# ecg_final.net
KiCad netlist of a schematic drawn in EAGLE
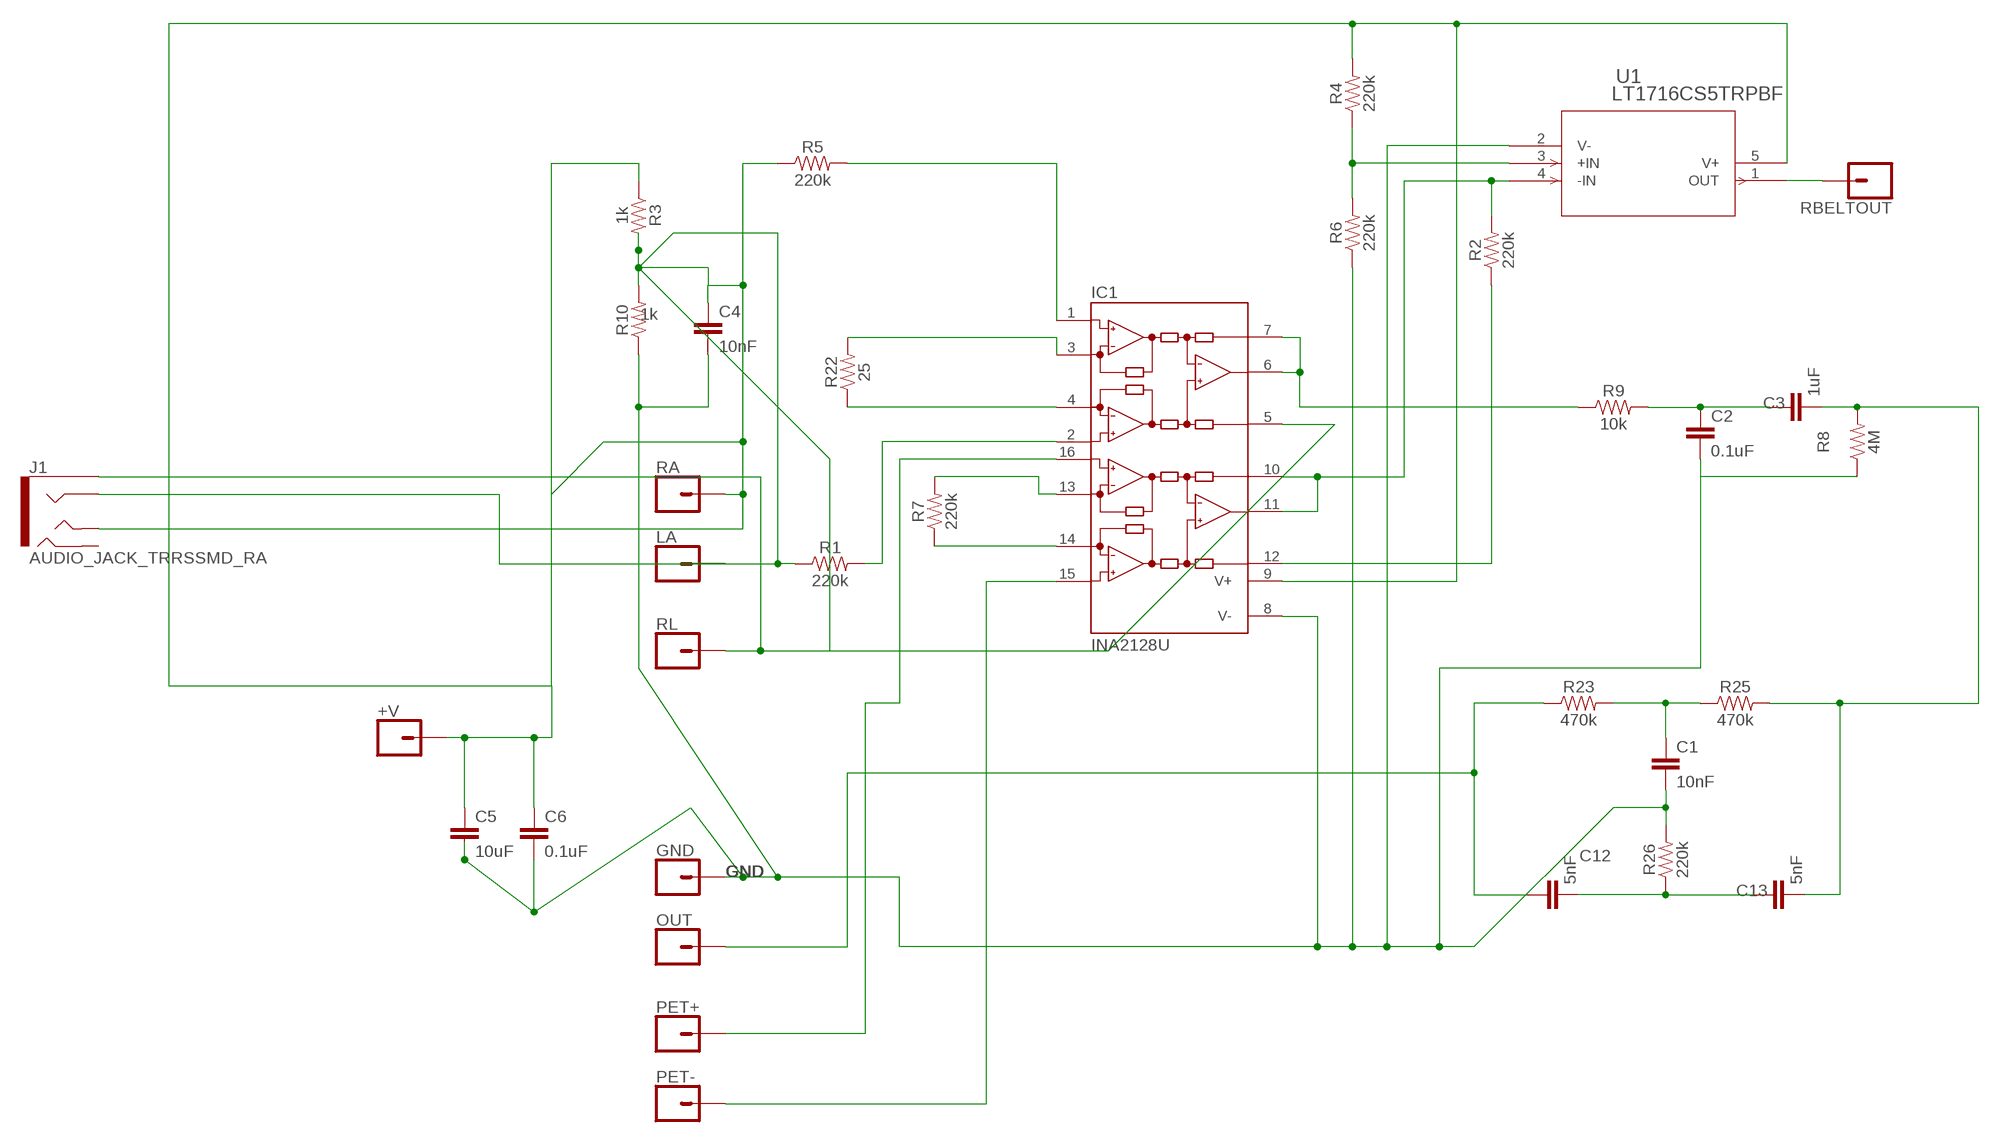
[diagram p0: schematic, sheet 1]

(export (version "E")
  (design (tool "Eeschema 10.0.6"))
  (components
    (comp (ref "+V")
      (value "CONN_01")
      (footprint "eagle-import:1X01")
      (libsource (lib "eagle-import") (part "CONN_01"))
    )
    (comp (ref "C1")
      (value "10nF")
      (footprint "eagle-import:CAP-PTH-10MM")
      (libsource (lib "eagle-import") (part "10NF-PTH-10MM-10000V-1-%"))
    )
    (comp (ref "C2")
      (value "0.1uF")
      (footprint "eagle-import:CAP-PTH-10MM")
      (libsource (lib "eagle-import") (part "10NF-PTH-10MM-10000V-1-%"))
    )
    (comp (ref "C3")
      (value "1uF")
      (footprint "eagle-import:CAP-PTH-10MM")
      (libsource (lib "eagle-import") (part "10NF-PTH-10MM-10000V-1-%"))
    )
    (comp (ref "C4")
      (value "10nF")
      (footprint "eagle-import:CAP-PTH-10MM")
      (libsource (lib "eagle-import") (part "10NF-PTH-10MM-10000V-1-%"))
    )
    (comp (ref "C5")
      (value "10uF")
      (footprint "eagle-import:CAP-PTH-10MM")
      (libsource (lib "eagle-import") (part "10NF-PTH-10MM-10000V-1-%"))
    )
    (comp (ref "C6")
      (value "0.1uF")
      (footprint "eagle-import:CAP-PTH-10MM")
      (libsource (lib "eagle-import") (part "10NF-PTH-10MM-10000V-1-%"))
    )
    (comp (ref "C12")
      (value "5nF")
      (footprint "eagle-import:CAP-PTH-10MM")
      (libsource (lib "eagle-import") (part "10NF-PTH-10MM-10000V-1-%"))
    )
    (comp (ref "C13")
      (value "5nF")
      (footprint "eagle-import:CAP-PTH-10MM")
      (libsource (lib "eagle-import") (part "10NF-PTH-10MM-10000V-1-%"))
    )
    (comp (ref "GND")
      (value "CONN_01")
      (footprint "eagle-import:1X01")
      (libsource (lib "eagle-import") (part "CONN_01"))
    )
    (comp (ref "IC1")
      (value "INA2128U")
      (footprint "eagle-import:SO16-1")
      (fields (field (name "MF") "TEXAS INSTRUMENTS"))
      (libsource (lib "eagle-import") (part "INA2128U"))
    )
    (comp (ref "J1")
      (value "AUDIO_JACK_TRRSSMD_RA")
      (footprint "eagle-import:AUDIO_JACK_3.5MM_TRRS_SMD_RA")
      (libsource (lib "eagle-import") (part "AUDIO_JACK_TRRSSMD_RA"))
    )
    (comp (ref "LA")
      (value "CONN_01")
      (footprint "eagle-import:1X01")
      (libsource (lib "eagle-import") (part "CONN_01"))
    )
    (comp (ref "OUT")
      (value "CONN_01")
      (footprint "eagle-import:1X01")
      (libsource (lib "eagle-import") (part "CONN_01"))
    )
    (comp (ref "PET+")
      (value "CONN_01")
      (footprint "eagle-import:1X01")
      (libsource (lib "eagle-import") (part "CONN_01"))
    )
    (comp (ref "PET-")
      (value "CONN_01")
      (footprint "eagle-import:1X01")
      (libsource (lib "eagle-import") (part "CONN_01"))
    )
    (comp (ref "R1")
      (value "220k")
      (footprint "eagle-import:AXIAL-0.3")
      (libsource (lib "eagle-import") (part "10KOHM-HORIZ-1/4W-1%"))
    )
    (comp (ref "R2")
      (value "220k")
      (footprint "eagle-import:AXIAL-0.3")
      (libsource (lib "eagle-import") (part "10KOHM-HORIZ-1/4W-1%"))
    )
    (comp (ref "R3")
      (value "1k")
      (footprint "eagle-import:AXIAL-0.3")
      (libsource (lib "eagle-import") (part "1KOHM-HORIZ-1/4W-1%"))
    )
    (comp (ref "R4")
      (value "220k")
      (footprint "eagle-import:AXIAL-0.3")
      (libsource (lib "eagle-import") (part "10KOHM-HORIZ-1/4W-1%"))
    )
    (comp (ref "R5")
      (value "220k")
      (footprint "eagle-import:AXIAL-0.3")
      (libsource (lib "eagle-import") (part "10KOHM-HORIZ-1/4W-1%"))
    )
    (comp (ref "R6")
      (value "220k")
      (footprint "eagle-import:AXIAL-0.3")
      (libsource (lib "eagle-import") (part "10KOHM-HORIZ-1/4W-1%"))
    )
    (comp (ref "R7")
      (value "220k")
      (footprint "eagle-import:AXIAL-0.3")
      (libsource (lib "eagle-import") (part "10KOHM-HORIZ-1/4W-1%"))
    )
    (comp (ref "R8")
      (value "4M")
      (footprint "eagle-import:AXIAL-0.3")
      (libsource (lib "eagle-import") (part "1KOHM-HORIZ-1/4W-1%"))
    )
    (comp (ref "R9")
      (value "10k")
      (footprint "eagle-import:AXIAL-0.3")
      (libsource (lib "eagle-import") (part "1KOHM-HORIZ-1/4W-1%"))
    )
    (comp (ref "R10")
      (value "1k")
      (footprint "eagle-import:AXIAL-0.3")
      (libsource (lib "eagle-import") (part "1KOHM-HORIZ-1/4W-1%"))
    )
    (comp (ref "R22")
      (value "25")
      (footprint "eagle-import:AXIAL-0.3")
      (libsource (lib "eagle-import") (part "1KOHM-HORIZ-1/4W-5%"))
    )
    (comp (ref "R23")
      (value "470k")
      (footprint "eagle-import:AXIAL-0.3")
      (libsource (lib "eagle-import") (part "1KOHM-HORIZ-1/4W-5%"))
    )
    (comp (ref "R25")
      (value "470k")
      (footprint "eagle-import:AXIAL-0.3")
      (libsource (lib "eagle-import") (part "1KOHM-HORIZ-1/4W-5%"))
    )
    (comp (ref "R26")
      (value "220k")
      (footprint "eagle-import:AXIAL-0.3")
      (libsource (lib "eagle-import") (part "1KOHM-HORIZ-1/4W-5%"))
    )
    (comp (ref "RA")
      (value "CONN_01")
      (footprint "eagle-import:1X01")
      (libsource (lib "eagle-import") (part "CONN_01"))
    )
    (comp (ref "RBELTOUT")
      (value "CONN_01")
      (footprint "eagle-import:1X01")
      (libsource (lib "eagle-import") (part "CONN_01"))
    )
    (comp (ref "RL")
      (value "CONN_01")
      (footprint "eagle-import:1X01")
      (libsource (lib "eagle-import") (part "CONN_01"))
    )
    (comp (ref "U1")
      (value "LT1716CS5TRPBF")
      (footprint "eagle-import:SOT-5_S")
      (fields
        (field (name "DIGI-KEY_PART_NUMBER") "LT1716CS5#TRPBFCT-ND")
        (field (name "MF") "Linear Technology")
        (field (name "MP") "LT1716CS5#TRPBF")
      )
      (libsource (lib "eagle-import") (part "LT1716CS5TRPBF"))
    )
  )
  (nets
    (net (code "1") (name "/GND") (class "Default")
      (node (ref "C1") (pin "2") (pinfunction "2_2") (pintype "passive"))
      (node (ref "C2") (pin "2") (pinfunction "2_2") (pintype "passive"))
      (node (ref "C4") (pin "2") (pinfunction "2_2") (pintype "passive"))
      (node (ref "C5") (pin "2") (pinfunction "2_2") (pintype "passive"))
      (node (ref "C6") (pin "2") (pinfunction "2_2") (pintype "passive"))
      (node (ref "GND") (pin "1") (pinfunction "1_1") (pintype "passive"))
      (node (ref "IC1") (pin "8") (pinfunction "V-_8") (pintype "power_in"))
      (node (ref "R10") (pin "P$1") (pinfunction "1_P$1") (pintype "passive"))
      (node (ref "R26") (pin "P$2") (pinfunction "2_P$2") (pintype "passive"))
      (node (ref "R6") (pin "P$1") (pinfunction "1_P$1") (pintype "passive"))
      (node (ref "R8") (pin "P$1") (pinfunction "1_P$1") (pintype "passive"))
      (node (ref "U1") (pin "2") (pinfunction "V-_2") (pintype "power_in"))
    )
    (net (code "2") (name "Net-(IC1-INA+)") (class "Default")
      (node (ref "IC1") (pin "2") (pinfunction "INA+_2") (pintype "input"))
      (node (ref "R1") (pin "P$2") (pinfunction "2_P$2") (pintype "passive"))
    )
    (net (code "3") (name "Net-(IC1-INA-)") (class "Default")
      (node (ref "IC1") (pin "1") (pinfunction "INA-_1") (pintype "input"))
      (node (ref "R5") (pin "P$2") (pinfunction "2_P$2") (pintype "passive"))
    )
    (net (code "4") (name "Net-(IC1-INB+)") (class "Default")
      (node (ref "IC1") (pin "15") (pinfunction "INB+_15") (pintype "input"))
      (node (ref "PET-") (pin "1") (pinfunction "1_1") (pintype "passive"))
    )
    (net (code "5") (name "Net-(IC1-INB-)") (class "Default")
      (node (ref "IC1") (pin "16") (pinfunction "INB-_16") (pintype "input"))
      (node (ref "PET+") (pin "1") (pinfunction "1_1") (pintype "passive"))
    )
    (net (code "6") (name "Net-(IC1-REFA)") (class "Default")
      (node (ref "C4") (pin "1") (pinfunction "1_1") (pintype "passive"))
      (node (ref "IC1") (pin "5") (pinfunction "REFA_5") (pintype "input"))
      (node (ref "J1") (pin "EARTH") (pinfunction "EARTH_EARTH") (pintype "bidirectional"))
      (node (ref "J1") (pin "RING1") (pinfunction "RING1_RING1") (pintype "bidirectional"))
      (node (ref "J1") (pin "TIP") (pinfunction "TIP_TIP") (pintype "bidirectional"))
      (node (ref "LA") (pin "1") (pinfunction "1_1") (pintype "passive"))
      (node (ref "R1") (pin "P$1") (pinfunction "1_P$1") (pintype "passive"))
      (node (ref "R10") (pin "P$2") (pinfunction "2_P$2") (pintype "passive"))
      (node (ref "R3") (pin "P$2") (pinfunction "2_P$2") (pintype "passive"))
      (node (ref "R5") (pin "P$1") (pinfunction "1_P$1") (pintype "passive"))
      (node (ref "RA") (pin "1") (pinfunction "1_1") (pintype "passive"))
      (node (ref "RL") (pin "1") (pinfunction "1_1") (pintype "passive"))
    )
    (net (code "7") (name "Net-(IC1-REFB)") (class "Default")
      (node (ref "IC1") (pin "12") (pinfunction "REFB_12") (pintype "input"))
      (node (ref "R2") (pin "P$1") (pinfunction "1_P$1") (pintype "passive"))
    )
    (net (code "8") (name "Net-(IC1-SENSEA)") (class "Default")
      (node (ref "IC1") (pin "6") (pinfunction "VOA_6") (pintype "output"))
      (node (ref "IC1") (pin "7") (pinfunction "SENSEA_7") (pintype "input"))
      (node (ref "R9") (pin "P$1") (pinfunction "1_P$1") (pintype "passive"))
    )
    (net (code "9") (name "Net-(IC1-SENSEB)") (class "Default")
      (node (ref "IC1") (pin "10") (pinfunction "SENSEB_10") (pintype "input"))
      (node (ref "IC1") (pin "11") (pinfunction "VOB_11") (pintype "output"))
      (node (ref "R2") (pin "P$2") (pinfunction "2_P$2") (pintype "passive"))
      (node (ref "U1") (pin "4") (pinfunction "-IN_4") (pintype "input"))
    )
    (net (code "10") (name "Net-(IC1-V+)") (class "Default")
      (node (ref "+V") (pin "1") (pinfunction "1_1") (pintype "passive"))
      (node (ref "C5") (pin "1") (pinfunction "1_1") (pintype "passive"))
      (node (ref "C6") (pin "1") (pinfunction "1_1") (pintype "passive"))
      (node (ref "IC1") (pin "9") (pinfunction "V+_9") (pintype "power_in"))
      (node (ref "R3") (pin "P$1") (pinfunction "1_P$1") (pintype "passive"))
      (node (ref "R4") (pin "P$2") (pinfunction "2_P$2") (pintype "passive"))
      (node (ref "U1") (pin "5") (pinfunction "V+_5") (pintype "power_in"))
    )
    (net (code "11") (name "Net-(R4-1)") (class "Default")
      (node (ref "R4") (pin "P$1") (pinfunction "1_P$1") (pintype "passive"))
      (node (ref "R6") (pin "P$2") (pinfunction "2_P$2") (pintype "passive"))
      (node (ref "U1") (pin "3") (pinfunction "+IN_3") (pintype "input"))
    )
    (net (code "12") (name "Net-(R7-1)") (class "Default")
      (node (ref "IC1") (pin "14") (pinfunction "RGB_14") (pintype "passive"))
      (node (ref "R7") (pin "P$1") (pinfunction "1_P$1") (pintype "passive"))
    )
    (net (code "13") (name "Net-(R7-2)") (class "Default")
      (node (ref "IC1") (pin "13") (pinfunction "RGB_13") (pintype "passive"))
      (node (ref "R7") (pin "P$2") (pinfunction "2_P$2") (pintype "passive"))
    )
    (net (code "14") (name "Net-(R9-2)") (class "Default")
      (node (ref "C2") (pin "1") (pinfunction "1_1") (pintype "passive"))
      (node (ref "C3") (pin "1") (pinfunction "1_1") (pintype "passive"))
      (node (ref "R9") (pin "P$2") (pinfunction "2_P$2") (pintype "passive"))
    )
    (net (code "15") (name "Net-(R22-1)") (class "Default")
      (node (ref "IC1") (pin "4") (pinfunction "RGA_4") (pintype "passive"))
      (node (ref "R22") (pin "P$1") (pinfunction "1_P$1") (pintype "passive"))
    )
    (net (code "16") (name "Net-(R22-2)") (class "Default")
      (node (ref "IC1") (pin "3") (pinfunction "RGA_3") (pintype "passive"))
      (node (ref "R22") (pin "P$2") (pinfunction "2_P$2") (pintype "passive"))
    )
    (net (code "17") (name "Net-(R23-1)") (class "Default")
      (node (ref "C12") (pin "1") (pinfunction "1_1") (pintype "passive"))
      (node (ref "OUT") (pin "1") (pinfunction "1_1") (pintype "passive"))
      (node (ref "R23") (pin "P$1") (pinfunction "1_P$1") (pintype "passive"))
    )
    (net (code "18") (name "Net-(R23-2)") (class "Default")
      (node (ref "C1") (pin "1") (pinfunction "1_1") (pintype "passive"))
      (node (ref "R23") (pin "P$2") (pinfunction "2_P$2") (pintype "passive"))
      (node (ref "R25") (pin "P$1") (pinfunction "1_P$1") (pintype "passive"))
    )
    (net (code "19") (name "Net-(R25-2)") (class "Default")
      (node (ref "C13") (pin "2") (pinfunction "2_2") (pintype "passive"))
      (node (ref "C3") (pin "2") (pinfunction "2_2") (pintype "passive"))
      (node (ref "R25") (pin "P$2") (pinfunction "2_P$2") (pintype "passive"))
      (node (ref "R8") (pin "P$2") (pinfunction "2_P$2") (pintype "passive"))
    )
    (net (code "20") (name "Net-(R26-1)") (class "Default")
      (node (ref "C12") (pin "2") (pinfunction "2_2") (pintype "passive"))
      (node (ref "C13") (pin "1") (pinfunction "1_1") (pintype "passive"))
      (node (ref "R26") (pin "P$1") (pinfunction "1_P$1") (pintype "passive"))
    )
    (net (code "21") (name "Net-(U1-OUT)") (class "Default")
      (node (ref "RBELTOUT") (pin "1") (pinfunction "1_1") (pintype "passive"))
      (node (ref "U1") (pin "1") (pinfunction "OUT_1") (pintype "output"))
    )
    (net (code "22") (name "unconnected-(J1-PadRING2)") (class "Default")
      (node (ref "J1") (pin "RING2") (pinfunction "RING2_RING2") (pintype "bidirectional"))
    )
  )
)
